# motor_controller_schV2.net
KiCad netlist of a schematic drawn in EAGLE
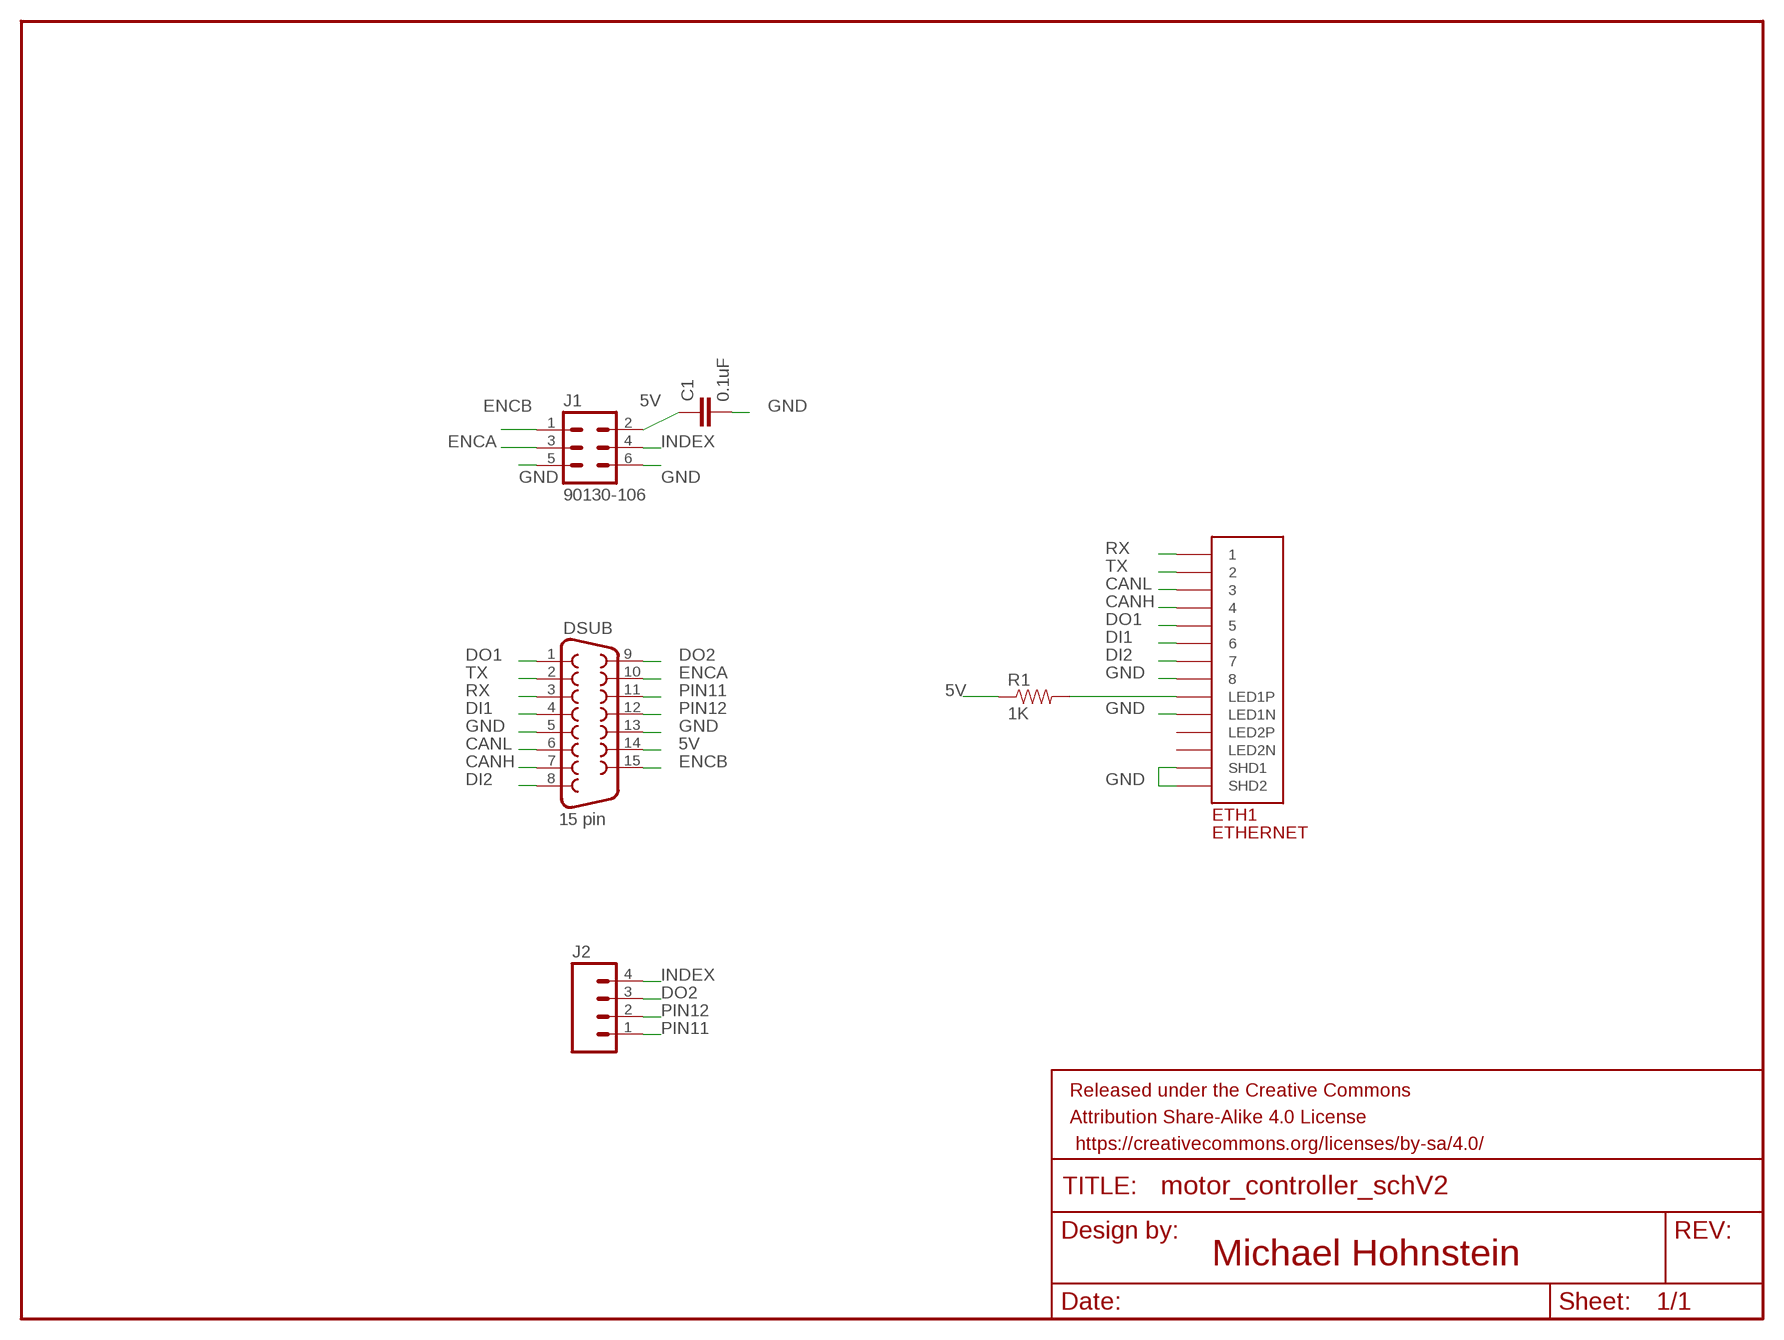
[diagram p0: schematic, sheet 1]

(export (version "E")
  (design (tool "Eeschema 10.0.6"))
  (components
    (comp (ref "C1")
      (value "0.1uF")
      (footprint "eagle-import:0603-CAP")
      (libsource (lib "eagle-import") (part "0.1UF-25V(+80/-20%)(0603)"))
    )
    (comp (ref "DSUB")
      (value "15 pin")
      (footprint "eagle-import:F15HP")
      (libsource (lib "eagle-import") (part "F15HP"))
    )
    (comp (ref "ETH1")
      (value "ETHERNET")
      (footprint "eagle-import:A122645-ND")
      (libsource (lib "eagle-import") (part "ETHERNET"))
    )
    (comp (ref "FRAME1")
      (value "FRAME-LETTER")
      (footprint "eagle-import:CREATIVE_COMMONS")
      (libsource (lib "eagle-import") (part "FRAME-LETTER"))
    )
    (comp (ref "J1")
      (value "90130-106")
      (footprint "eagle-import:90130-1_06")
      (libsource (lib "eagle-import") (part "90130-1?06"))
    )
    (comp (ref "J2")
      (value "M04PTH")
      (footprint "eagle-import:1X04")
      (libsource (lib "eagle-import") (part "M04PTH"))
    )
    (comp (ref "R1")
      (value "1K")
      (footprint "eagle-import:0603-RES")
      (libsource (lib "eagle-import") (part "1KOHM-1/10W-1%(0603)"))
    )
  )
  (nets
    (net (code "1") (name "/5V") (class "Default")
      (node (ref "C1") (pin "1") (pinfunction "1_1") (pintype "passive"))
      (node (ref "DSUB") (pin "14") (pinfunction "14_14") (pintype "passive"))
      (node (ref "J1") (pin "2") (pinfunction "2_2") (pintype "passive"))
      (node (ref "R1") (pin "1") (pinfunction "1_1") (pintype "passive"))
    )
    (net (code "2") (name "/CANH") (class "Default")
      (node (ref "DSUB") (pin "7") (pinfunction "7_7") (pintype "passive"))
      (node (ref "ETH1") (pin "P$4") (pinfunction "4_P$4") (pintype "bidirectional"))
    )
    (net (code "3") (name "/CANL") (class "Default")
      (node (ref "DSUB") (pin "6") (pinfunction "6_6") (pintype "passive"))
      (node (ref "ETH1") (pin "P$3") (pinfunction "3_P$3") (pintype "bidirectional"))
    )
    (net (code "4") (name "/DI1") (class "Default")
      (node (ref "DSUB") (pin "4") (pinfunction "4_4") (pintype "passive"))
      (node (ref "ETH1") (pin "P$6") (pinfunction "6_P$6") (pintype "bidirectional"))
    )
    (net (code "5") (name "/DI2") (class "Default")
      (node (ref "DSUB") (pin "8") (pinfunction "8_8") (pintype "passive"))
      (node (ref "ETH1") (pin "P$7") (pinfunction "7_P$7") (pintype "bidirectional"))
    )
    (net (code "6") (name "/DO1") (class "Default")
      (node (ref "DSUB") (pin "1") (pinfunction "1_1") (pintype "passive"))
      (node (ref "ETH1") (pin "P$5") (pinfunction "5_P$5") (pintype "bidirectional"))
    )
    (net (code "7") (name "/DO2") (class "Default")
      (node (ref "DSUB") (pin "9") (pinfunction "9_9") (pintype "passive"))
      (node (ref "J2") (pin "3") (pinfunction "3_3") (pintype "passive"))
    )
    (net (code "8") (name "/ENCA") (class "Default")
      (node (ref "DSUB") (pin "10") (pinfunction "10_10") (pintype "passive"))
      (node (ref "J1") (pin "3") (pinfunction "3_3") (pintype "passive"))
    )
    (net (code "9") (name "/ENCB") (class "Default")
      (node (ref "DSUB") (pin "15") (pinfunction "15_15") (pintype "passive"))
      (node (ref "J1") (pin "1") (pinfunction "1_1") (pintype "passive"))
    )
    (net (code "10") (name "/GND") (class "Default")
      (node (ref "C1") (pin "2") (pinfunction "2_2") (pintype "passive"))
      (node (ref "DSUB") (pin "13") (pinfunction "13_13") (pintype "passive"))
      (node (ref "DSUB") (pin "5") (pinfunction "5_5") (pintype "passive"))
      (node (ref "ETH1") (pin "P$13") (pinfunction "SHD1_P$13") (pintype "bidirectional"))
      (node (ref "ETH1") (pin "P$14") (pinfunction "SHD2_P$14") (pintype "bidirectional"))
      (node (ref "ETH1") (pin "P$8") (pinfunction "8_P$8") (pintype "bidirectional"))
      (node (ref "ETH1") (pin "P$9") (pinfunction "LED1N_P$9") (pintype "bidirectional"))
      (node (ref "J1") (pin "5") (pinfunction "5_5") (pintype "passive"))
      (node (ref "J1") (pin "6") (pinfunction "6_6") (pintype "passive"))
    )
    (net (code "11") (name "/INDEX") (class "Default")
      (node (ref "J1") (pin "4") (pinfunction "4_4") (pintype "passive"))
      (node (ref "J2") (pin "4") (pinfunction "4_4") (pintype "passive"))
    )
    (net (code "12") (name "/PIN11") (class "Default")
      (node (ref "DSUB") (pin "11") (pinfunction "11_11") (pintype "passive"))
      (node (ref "J2") (pin "1") (pinfunction "1_1") (pintype "passive"))
    )
    (net (code "13") (name "/PIN12") (class "Default")
      (node (ref "DSUB") (pin "12") (pinfunction "12_12") (pintype "passive"))
      (node (ref "J2") (pin "2") (pinfunction "2_2") (pintype "passive"))
    )
    (net (code "14") (name "/RX") (class "Default")
      (node (ref "DSUB") (pin "3") (pinfunction "3_3") (pintype "passive"))
      (node (ref "ETH1") (pin "P$1") (pinfunction "1_P$1") (pintype "bidirectional"))
    )
    (net (code "15") (name "/TX") (class "Default")
      (node (ref "DSUB") (pin "2") (pinfunction "2_2") (pintype "passive"))
      (node (ref "ETH1") (pin "P$2") (pinfunction "2_P$2") (pintype "bidirectional"))
    )
    (net (code "16") (name "Net-(ETH1-LED1P)") (class "Default")
      (node (ref "ETH1") (pin "P$10") (pinfunction "LED1P_P$10") (pintype "bidirectional"))
      (node (ref "R1") (pin "2") (pinfunction "2_2") (pintype "passive"))
    )
    (net (code "17") (name "unconnected-(ETH1-LED2N-PadP$11)") (class "Default")
      (node (ref "ETH1") (pin "P$11") (pinfunction "LED2N_P$11") (pintype "bidirectional"))
    )
    (net (code "18") (name "unconnected-(ETH1-LED2P-PadP$12)") (class "Default")
      (node (ref "ETH1") (pin "P$12") (pinfunction "LED2P_P$12") (pintype "bidirectional"))
    )
  )
)
